# KNoT-Gateway_Mini_Starter_Board.net
KiCad netlist of a schematic drawn in Altium Designer
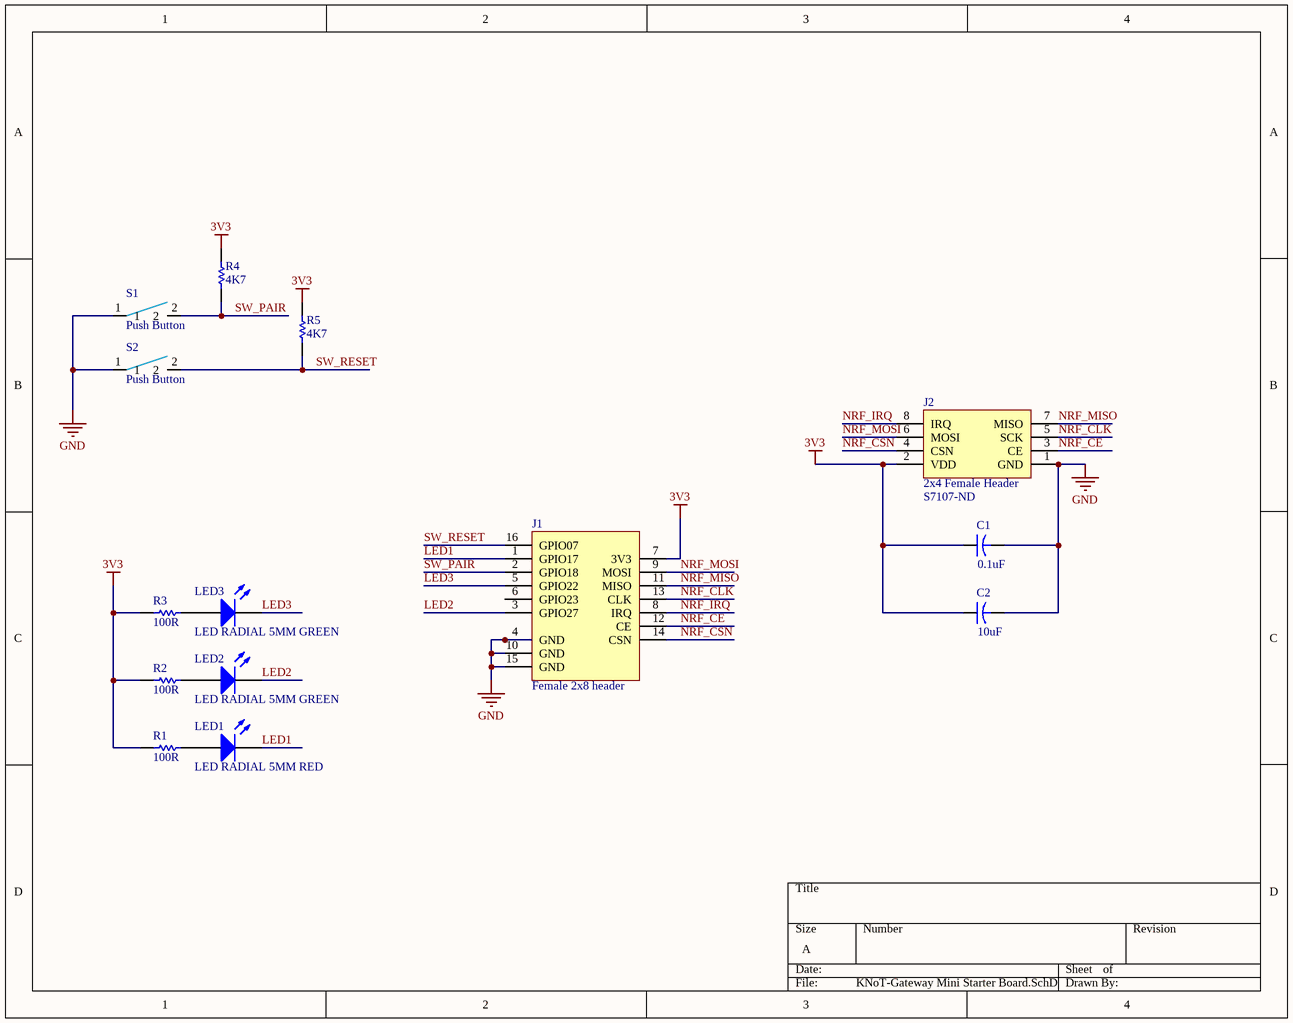
[diagram p0: KNoT-Gateway Mini Starter Board.SchDoc]

(export (version "E")
  (design (tool "Eeschema 10.0.6"))
  (components
    (comp (ref "C1")
      (value "0.1uF")
      (footprint "0805_CAPS")
      (description "0.1µF  Ceramic Capacitor 0805")
      (fields (field (name "Comment") "Cap 0805 0.1uF"))
      (libsource (lib "KNoT-Gateway Library") (part "Cap_0805_0.1uF"))
    )
    (comp (ref "C2")
      (value "10uF")
      (footprint "0805_CAPS")
      (description "10uF Ceramic Capacitor 0805")
      (fields (field (name "Comment") "Cap 0805 10uF"))
      (libsource (lib "KNoT-Gateway Library") (part "Cap_0805_10uF"))
    )
    (comp (ref "J1")
      (value "Female 2x8 header")
      (footprint "FEMALE HEADER 2X8")
      (description "Female Bottom 2x4 Header")
      (libsource (lib "KNoT-Gateway Library") (part "2x8 RPi Header"))
    )
    (comp (ref "J2")
      (value "2x4 Female Header")
      (footprint "nRF24L01+PA+LNA")
      (description "nRF24L01 2x4 HEADER")
      (fields (field (name "SUPPLIER PART NUMBER 1") "S7107-ND"))
      (libsource (lib "KNoT-Gateway Library") (part "nRF24L01+"))
    )
    (comp (ref "LED1")
      (value "LED RADIAL 5MM RED")
      (footprint "LED RADIAL 5MM RED")
      (description "LED RADIAL")
      (libsource (lib "KNoT-Gateway Library") (part "LED RADIAL 5MM RED"))
    )
    (comp (ref "LED2")
      (value "LED RADIAL 5MM GREEN")
      (footprint "LED RADIAL 5MM GREEN")
      (description "LED RADIAL")
      (libsource (lib "KNoT-Gateway Library") (part "LED RADIAL 5MM GREEN"))
    )
    (comp (ref "LED3")
      (value "LED RADIAL 5MM GREEN")
      (footprint "LED RADIAL 5MM GREEN")
      (description "LED RADIAL")
      (libsource (lib "KNoT-Gateway Library") (part "LED RADIAL 5MM GREEN"))
    )
    (comp (ref "R1")
      (value "100R")
      (footprint "0805_RES")
      (fields (field (name "Comment") "RES_0805"))
      (libsource (lib "KNoT-Gateway Library") (part "RES_0805"))
    )
    (comp (ref "R2")
      (value "100R")
      (footprint "0805_RES")
      (fields (field (name "Comment") "RES_0805"))
      (libsource (lib "KNoT-Gateway Library") (part "RES_0805"))
    )
    (comp (ref "R3")
      (value "100R")
      (footprint "0805_RES")
      (fields (field (name "Comment") "RES_0805"))
      (libsource (lib "KNoT-Gateway Library") (part "RES_0805"))
    )
    (comp (ref "R4")
      (value "4K7")
      (footprint "0805_RES")
      (fields (field (name "Comment") "RES_0805"))
      (libsource (lib "KNoT-Gateway Library") (part "RES_0805"))
    )
    (comp (ref "R5")
      (value "4K7")
      (footprint "0805_RES")
      (fields (field (name "Comment") "RES_0805"))
      (libsource (lib "KNoT-Gateway Library") (part "RES_0805"))
    )
    (comp (ref "S1")
      (value "Push Button")
      (footprint "Tac Push Button L")
      (description "Tactile Push Button Right Angle")
      (libsource (lib "KNoT-Gateway Library") (part "Push Button L"))
    )
    (comp (ref "S2")
      (value "Push Button")
      (footprint "Tac Push Button S")
      (description "Tactile Push Button Right Angle")
      (libsource (lib "KNoT-Gateway Library") (part "Push Button S"))
    )
  )
  (nets
    (net (code "1") (name "/LED1") (class "Default")
      (node (ref "J1") (pin "1") (pinfunction "GPIO17_1") (pintype "passive"))
      (node (ref "LED1") (pin "2") (pinfunction "K_2") (pintype "passive"))
    )
    (net (code "2") (name "/LED2") (class "Default")
      (node (ref "J1") (pin "3") (pinfunction "GPIO27_3") (pintype "passive"))
      (node (ref "LED2") (pin "2") (pinfunction "K_2") (pintype "passive"))
    )
    (net (code "3") (name "/LED3") (class "Default")
      (node (ref "J1") (pin "5") (pinfunction "GPIO22_5") (pintype "passive"))
      (node (ref "LED3") (pin "2") (pinfunction "K_2") (pintype "passive"))
    )
    (net (code "4") (name "/NRF_CE") (class "Default")
      (node (ref "J1") (pin "12") (pinfunction "CE_12") (pintype "passive"))
      (node (ref "J2") (pin "3") (pinfunction "CE_3") (pintype "passive"))
    )
    (net (code "5") (name "/NRF_CLK") (class "Default")
      (node (ref "J1") (pin "13") (pinfunction "CLK_13") (pintype "passive"))
      (node (ref "J2") (pin "5") (pinfunction "SCK_5") (pintype "passive"))
    )
    (net (code "6") (name "/NRF_CSN") (class "Default")
      (node (ref "J1") (pin "14") (pinfunction "CSN_14") (pintype "passive"))
      (node (ref "J2") (pin "4") (pinfunction "CSN_4") (pintype "passive"))
    )
    (net (code "7") (name "/NRF_IRQ") (class "Default")
      (node (ref "J1") (pin "8") (pinfunction "IRQ_8") (pintype "passive"))
      (node (ref "J2") (pin "8") (pinfunction "IRQ_8") (pintype "passive"))
    )
    (net (code "8") (name "/NRF_MISO") (class "Default")
      (node (ref "J1") (pin "11") (pinfunction "MISO_11") (pintype "passive"))
      (node (ref "J2") (pin "7") (pinfunction "MISO_7") (pintype "passive"))
    )
    (net (code "9") (name "/NRF_MOSI") (class "Default")
      (node (ref "J1") (pin "9") (pinfunction "MOSI_9") (pintype "passive"))
      (node (ref "J2") (pin "6") (pinfunction "MOSI_6") (pintype "passive"))
    )
    (net (code "10") (name "/SW_PAIR") (class "Default")
      (node (ref "J1") (pin "2") (pinfunction "GPIO18_2") (pintype "passive"))
      (node (ref "R4") (pin "1") (pinfunction "1_1") (pintype "passive"))
      (node (ref "S1") (pin "2") (pinfunction "2_2") (pintype "passive"))
    )
    (net (code "11") (name "/SW_RESET") (class "Default")
      (node (ref "J1") (pin "16") (pinfunction "GPIO07_16") (pintype "passive"))
      (node (ref "R5") (pin "1") (pinfunction "1_1") (pintype "passive"))
      (node (ref "S2") (pin "2") (pinfunction "2_2") (pintype "passive"))
    )
    (net (code "12") (name "3V3") (class "Default")
      (node (ref "C1") (pin "1") (pinfunction "1_1") (pintype "passive"))
      (node (ref "C2") (pin "1") (pinfunction "1_1") (pintype "passive"))
      (node (ref "J1") (pin "7") (pinfunction "3V3_7") (pintype "passive"))
      (node (ref "J2") (pin "2") (pinfunction "VDD_2") (pintype "passive"))
      (node (ref "R1") (pin "2") (pinfunction "2_2") (pintype "passive"))
      (node (ref "R2") (pin "2") (pinfunction "2_2") (pintype "passive"))
      (node (ref "R3") (pin "2") (pinfunction "2_2") (pintype "passive"))
      (node (ref "R4") (pin "2") (pinfunction "2_2") (pintype "passive"))
      (node (ref "R5") (pin "2") (pinfunction "2_2") (pintype "passive"))
    )
    (net (code "13") (name "GND") (class "Default")
      (node (ref "C1") (pin "2") (pinfunction "2_2") (pintype "passive"))
      (node (ref "C2") (pin "2") (pinfunction "2_2") (pintype "passive"))
      (node (ref "J1") (pin "10") (pinfunction "GND_10") (pintype "passive"))
      (node (ref "J1") (pin "15") (pinfunction "GND_15") (pintype "passive"))
      (node (ref "J1") (pin "4") (pinfunction "GND_4") (pintype "passive"))
      (node (ref "J2") (pin "1") (pinfunction "GND_1") (pintype "passive"))
      (node (ref "S1") (pin "1") (pinfunction "1_1") (pintype "passive"))
      (node (ref "S2") (pin "1") (pinfunction "1_1") (pintype "passive"))
    )
    (net (code "14") (name "Net-(LED1-A)") (class "Default")
      (node (ref "LED1") (pin "1") (pinfunction "A_1") (pintype "passive"))
      (node (ref "R1") (pin "1") (pinfunction "1_1") (pintype "passive"))
    )
    (net (code "15") (name "Net-(LED2-A)") (class "Default")
      (node (ref "LED2") (pin "1") (pinfunction "A_1") (pintype "passive"))
      (node (ref "R2") (pin "1") (pinfunction "1_1") (pintype "passive"))
    )
    (net (code "16") (name "Net-(LED3-A)") (class "Default")
      (node (ref "LED3") (pin "1") (pinfunction "A_1") (pintype "passive"))
      (node (ref "R3") (pin "1") (pinfunction "1_1") (pintype "passive"))
    )
    (net (code "17") (name "unconnected-(J1-GPIO23-Pad6)") (class "Default")
      (node (ref "J1") (pin "6") (pinfunction "GPIO23_6") (pintype "passive"))
    )
  )
)
